# Evap-Lite_V2_1.net
KiCad netlist of a schematic drawn in EAGLE
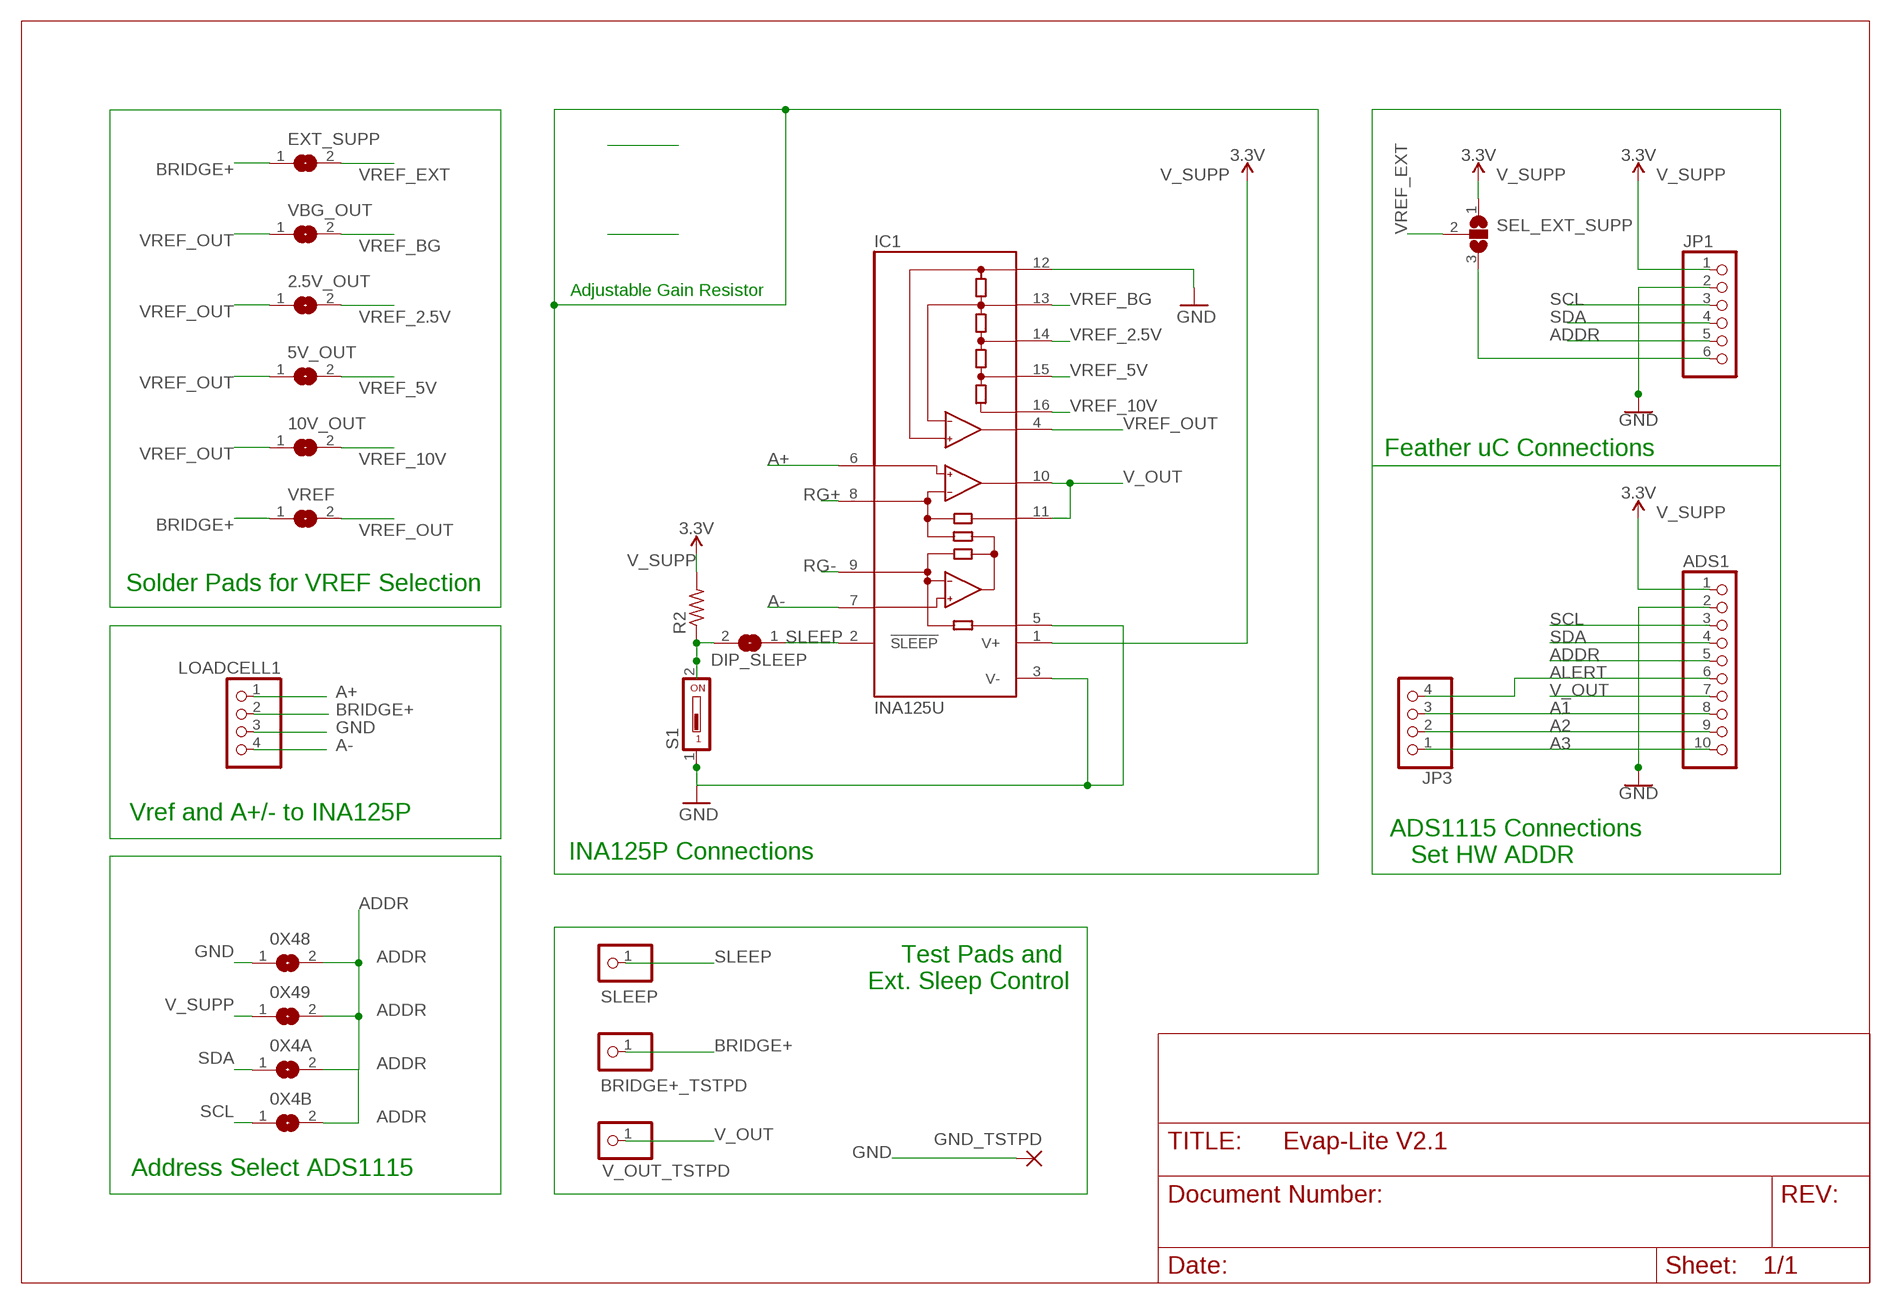
[diagram p0: schematic, sheet 1]

(export (version "E")
  (design (tool "Eeschema 10.0.6"))
  (components
    (comp (ref "0X4A")
      (value "SJ")
      (footprint "eagle-import:SJ")
      (libsource (lib "eagle-import") (part "SJ"))
    )
    (comp (ref "0X4B")
      (value "SJ")
      (footprint "eagle-import:SJ")
      (libsource (lib "eagle-import") (part "SJ"))
    )
    (comp (ref "0X48")
      (value "SJ")
      (footprint "eagle-import:SJ")
      (libsource (lib "eagle-import") (part "SJ"))
    )
    (comp (ref "0X49")
      (value "SJ")
      (footprint "eagle-import:SJ")
      (libsource (lib "eagle-import") (part "SJ"))
    )
    (comp (ref "2.5V_OUT")
      (value "SJ")
      (footprint "eagle-import:SJ")
      (libsource (lib "eagle-import") (part "SJ"))
    )
    (comp (ref "5V_OUT")
      (value "SJ")
      (footprint "eagle-import:SJ")
      (libsource (lib "eagle-import") (part "SJ"))
    )
    (comp (ref "10V_OUT")
      (value "SJ")
      (footprint "eagle-import:SJ")
      (libsource (lib "eagle-import") (part "SJ"))
    )
    (comp (ref "ADS1")
      (value "PINHD-1X10")
      (footprint "eagle-import:1X10")
      (libsource (lib "eagle-import") (part "PINHD-1X10"))
    )
    (comp (ref "BRIDGE+_TSTPD")
      (value "PINHD-1X1")
      (footprint "eagle-import:1X01")
      (libsource (lib "eagle-import") (part "PINHD-1X1"))
    )
    (comp (ref "DIP_SLEEP")
      (value "SJ")
      (footprint "eagle-import:SJ")
      (libsource (lib "eagle-import") (part "SJ"))
    )
    (comp (ref "EXT_SUPP")
      (value "SJ")
      (footprint "eagle-import:SJ")
      (libsource (lib "eagle-import") (part "SJ"))
    )
    (comp (ref "GND_TSTPD")
      (value "WIREPADSMD2,54-5,08")
      (footprint "eagle-import:SMD2,54-5,08")
      (libsource (lib "eagle-import") (part "WIREPADSMD2,54-5,08"))
    )
    (comp (ref "IC1")
      (value "INA125U")
      (footprint "eagle-import:SO16-1")
      (fields (field (name "MF") "TEXAS INSTRUMENT CONNECTORS"))
      (libsource (lib "eagle-import") (part "INA125U"))
    )
    (comp (ref "JP1")
      (value "PINHD-1X6")
      (footprint "eagle-import:1X06")
      (libsource (lib "eagle-import") (part "PINHD-1X6"))
    )
    (comp (ref "JP3")
      (value "PINHD-1X4")
      (footprint "eagle-import:1X04")
      (libsource (lib "eagle-import") (part "PINHD-1X4"))
    )
    (comp (ref "LOADCELL1")
      (value "PINHD-1X4")
      (footprint "eagle-import:1X04")
      (libsource (lib "eagle-import") (part "PINHD-1X4"))
    )
    (comp (ref "R2")
      (value "R-US_R1206")
      (footprint "eagle-import:R1206")
      (libsource (lib "eagle-import") (part "R-US_R1206"))
    )
    (comp (ref "S1")
      (value "DS01")
      (footprint "eagle-import:DS-01")
      (libsource (lib "eagle-import") (part "DS01"))
    )
    (comp (ref "SEL_EXT_SUPP")
      (value "SJ2WW")
      (footprint "eagle-import:SJ_2W")
      (libsource (lib "eagle-import") (part "SJ2WW"))
    )
    (comp (ref "SLEEP")
      (value "PINHD-1X1")
      (footprint "eagle-import:1X01")
      (libsource (lib "eagle-import") (part "PINHD-1X1"))
    )
    (comp (ref "VBG_OUT")
      (value "SJ")
      (footprint "eagle-import:SJ")
      (libsource (lib "eagle-import") (part "SJ"))
    )
    (comp (ref "VREF")
      (value "SJ")
      (footprint "eagle-import:SJ")
      (libsource (lib "eagle-import") (part "SJ"))
    )
    (comp (ref "V_OUT_TSTPD")
      (value "PINHD-1X1")
      (footprint "eagle-import:1X01")
      (libsource (lib "eagle-import") (part "PINHD-1X1"))
    )
  )
  (nets
    (net (code "1") (name "/A+") (class "Default")
      (node (ref "IC1") (pin "6") (pinfunction "+IN_6") (pintype "input"))
      (node (ref "LOADCELL1") (pin "1") (pinfunction "1_1") (pintype "passive"))
    )
    (net (code "2") (name "/A-") (class "Default")
      (node (ref "IC1") (pin "7") (pinfunction "-IN_7") (pintype "input"))
      (node (ref "LOADCELL1") (pin "4") (pinfunction "4_4") (pintype "passive"))
    )
    (net (code "3") (name "/A1") (class "Default")
      (node (ref "ADS1") (pin "8") (pinfunction "8_8") (pintype "passive"))
      (node (ref "JP3") (pin "3") (pinfunction "3_3") (pintype "passive"))
    )
    (net (code "4") (name "/A2") (class "Default")
      (node (ref "ADS1") (pin "9") (pinfunction "9_9") (pintype "passive"))
      (node (ref "JP3") (pin "2") (pinfunction "2_2") (pintype "passive"))
    )
    (net (code "5") (name "/A3") (class "Default")
      (node (ref "ADS1") (pin "10") (pinfunction "10_10") (pintype "passive"))
      (node (ref "JP3") (pin "1") (pinfunction "1_1") (pintype "passive"))
    )
    (net (code "6") (name "/ADDR") (class "Default")
      (node (ref "0X48") (pin "2") (pinfunction "2_2") (pintype "passive"))
      (node (ref "0X49") (pin "2") (pinfunction "2_2") (pintype "passive"))
      (node (ref "0X4A") (pin "2") (pinfunction "2_2") (pintype "passive"))
      (node (ref "0X4B") (pin "2") (pinfunction "2_2") (pintype "passive"))
      (node (ref "ADS1") (pin "5") (pinfunction "5_5") (pintype "passive"))
      (node (ref "JP1") (pin "5") (pinfunction "5_5") (pintype "passive"))
    )
    (net (code "7") (name "/ALERT") (class "Default")
      (node (ref "ADS1") (pin "6") (pinfunction "6_6") (pintype "passive"))
      (node (ref "JP3") (pin "4") (pinfunction "4_4") (pintype "passive"))
    )
    (net (code "8") (name "/BRIDGE+") (class "Default")
      (node (ref "BRIDGE+_TSTPD") (pin "1") (pinfunction "1_1") (pintype "passive"))
      (node (ref "EXT_SUPP") (pin "1") (pinfunction "1_1") (pintype "passive"))
      (node (ref "LOADCELL1") (pin "2") (pinfunction "2_2") (pintype "passive"))
      (node (ref "VREF") (pin "1") (pinfunction "1_1") (pintype "passive"))
    )
    (net (code "9") (name "/RG+") (class "Default")
      (node (ref "IC1") (pin "8") (pinfunction "RG_8") (pintype "passive"))
    )
    (net (code "10") (name "/RG-") (class "Default")
      (node (ref "IC1") (pin "9") (pinfunction "RG_9") (pintype "passive"))
    )
    (net (code "11") (name "/SCL") (class "Default")
      (node (ref "0X4B") (pin "1") (pinfunction "1_1") (pintype "passive"))
      (node (ref "ADS1") (pin "3") (pinfunction "3_3") (pintype "passive"))
      (node (ref "JP1") (pin "3") (pinfunction "3_3") (pintype "passive"))
    )
    (net (code "12") (name "/SDA") (class "Default")
      (node (ref "0X4A") (pin "1") (pinfunction "1_1") (pintype "passive"))
      (node (ref "ADS1") (pin "4") (pinfunction "4_4") (pintype "passive"))
      (node (ref "JP1") (pin "4") (pinfunction "4_4") (pintype "passive"))
    )
    (net (code "13") (name "/SLEEP") (class "Default")
      (node (ref "DIP_SLEEP") (pin "1") (pinfunction "1_1") (pintype "passive"))
      (node (ref "IC1") (pin "2") (pinfunction "~{SLEEP}_2") (pintype "input"))
      (node (ref "SLEEP") (pin "1") (pinfunction "1_1") (pintype "passive"))
    )
    (net (code "14") (name "/VREF_2.5V") (class "Default")
      (node (ref "2.5V_OUT") (pin "2") (pinfunction "2_2") (pintype "passive"))
      (node (ref "IC1") (pin "14") (pinfunction "REF2.5_14") (pintype "output"))
    )
    (net (code "15") (name "/VREF_5V") (class "Default")
      (node (ref "5V_OUT") (pin "2") (pinfunction "2_2") (pintype "passive"))
      (node (ref "IC1") (pin "15") (pinfunction "REF5_15") (pintype "output"))
    )
    (net (code "16") (name "/VREF_10V") (class "Default")
      (node (ref "10V_OUT") (pin "2") (pinfunction "2_2") (pintype "passive"))
      (node (ref "IC1") (pin "16") (pinfunction "REF10_16") (pintype "output"))
    )
    (net (code "17") (name "/VREF_BG") (class "Default")
      (node (ref "IC1") (pin "13") (pinfunction "REFBG_13") (pintype "output"))
      (node (ref "VBG_OUT") (pin "2") (pinfunction "2_2") (pintype "passive"))
    )
    (net (code "18") (name "/VREF_EXT") (class "Default")
      (node (ref "EXT_SUPP") (pin "2") (pinfunction "2_2") (pintype "passive"))
      (node (ref "SEL_EXT_SUPP") (pin "2") (pinfunction "2_2") (pintype "passive"))
    )
    (net (code "19") (name "/VREF_OUT") (class "Default")
      (node (ref "10V_OUT") (pin "1") (pinfunction "1_1") (pintype "passive"))
      (node (ref "2.5V_OUT") (pin "1") (pinfunction "1_1") (pintype "passive"))
      (node (ref "5V_OUT") (pin "1") (pinfunction "1_1") (pintype "passive"))
      (node (ref "IC1") (pin "4") (pinfunction "REFOUT_4") (pintype "output"))
      (node (ref "VBG_OUT") (pin "1") (pinfunction "1_1") (pintype "passive"))
      (node (ref "VREF") (pin "2") (pinfunction "2_2") (pintype "passive"))
    )
    (net (code "20") (name "/V_OUT") (class "Default")
      (node (ref "ADS1") (pin "7") (pinfunction "7_7") (pintype "passive"))
      (node (ref "IC1") (pin "10") (pinfunction "OUT_10") (pintype "output"))
      (node (ref "IC1") (pin "11") (pinfunction "SENSE_11") (pintype "passive"))
      (node (ref "V_OUT_TSTPD") (pin "1") (pinfunction "1_1") (pintype "passive"))
    )
    (net (code "21") (name "3.3V") (class "Default")
      (node (ref "0X49") (pin "1") (pinfunction "1_1") (pintype "passive"))
      (node (ref "ADS1") (pin "1") (pinfunction "1_1") (pintype "passive"))
      (node (ref "IC1") (pin "1") (pinfunction "V+_1") (pintype "power_in"))
      (node (ref "JP1") (pin "1") (pinfunction "1_1") (pintype "passive"))
      (node (ref "R2") (pin "2") (pinfunction "2_2") (pintype "passive"))
      (node (ref "SEL_EXT_SUPP") (pin "1") (pinfunction "1_1") (pintype "passive"))
    )
    (net (code "22") (name "GND") (class "Default")
      (node (ref "0X48") (pin "1") (pinfunction "1_1") (pintype "passive"))
      (node (ref "ADS1") (pin "2") (pinfunction "2_2") (pintype "passive"))
      (node (ref "GND_TSTPD") (pin "1") (pinfunction "P_1") (pintype "passive"))
      (node (ref "IC1") (pin "12") (pinfunction "REFCOM_12") (pintype "passive"))
      (node (ref "IC1") (pin "3") (pinfunction "V-_3") (pintype "power_in"))
      (node (ref "IC1") (pin "5") (pinfunction "REF_5") (pintype "passive"))
      (node (ref "JP1") (pin "2") (pinfunction "2_2") (pintype "passive"))
      (node (ref "LOADCELL1") (pin "3") (pinfunction "3_3") (pintype "passive"))
      (node (ref "S1") (pin "1") (pinfunction "1_1") (pintype "passive"))
    )
    (net (code "23") (name "Net-(DIP_SLEEP-Pad2)") (class "Default")
      (node (ref "DIP_SLEEP") (pin "2") (pinfunction "2_2") (pintype "passive"))
      (node (ref "R2") (pin "1") (pinfunction "1_1") (pintype "passive"))
      (node (ref "S1") (pin "2") (pinfunction "2_2") (pintype "passive"))
    )
    (net (code "24") (name "Net-(JP1-Pad6)") (class "Default")
      (node (ref "JP1") (pin "6") (pinfunction "6_6") (pintype "passive"))
      (node (ref "SEL_EXT_SUPP") (pin "3") (pinfunction "3_3") (pintype "passive"))
    )
  )
)
